# debugger.net
KiCad netlist of a schematic drawn in Altium Designer
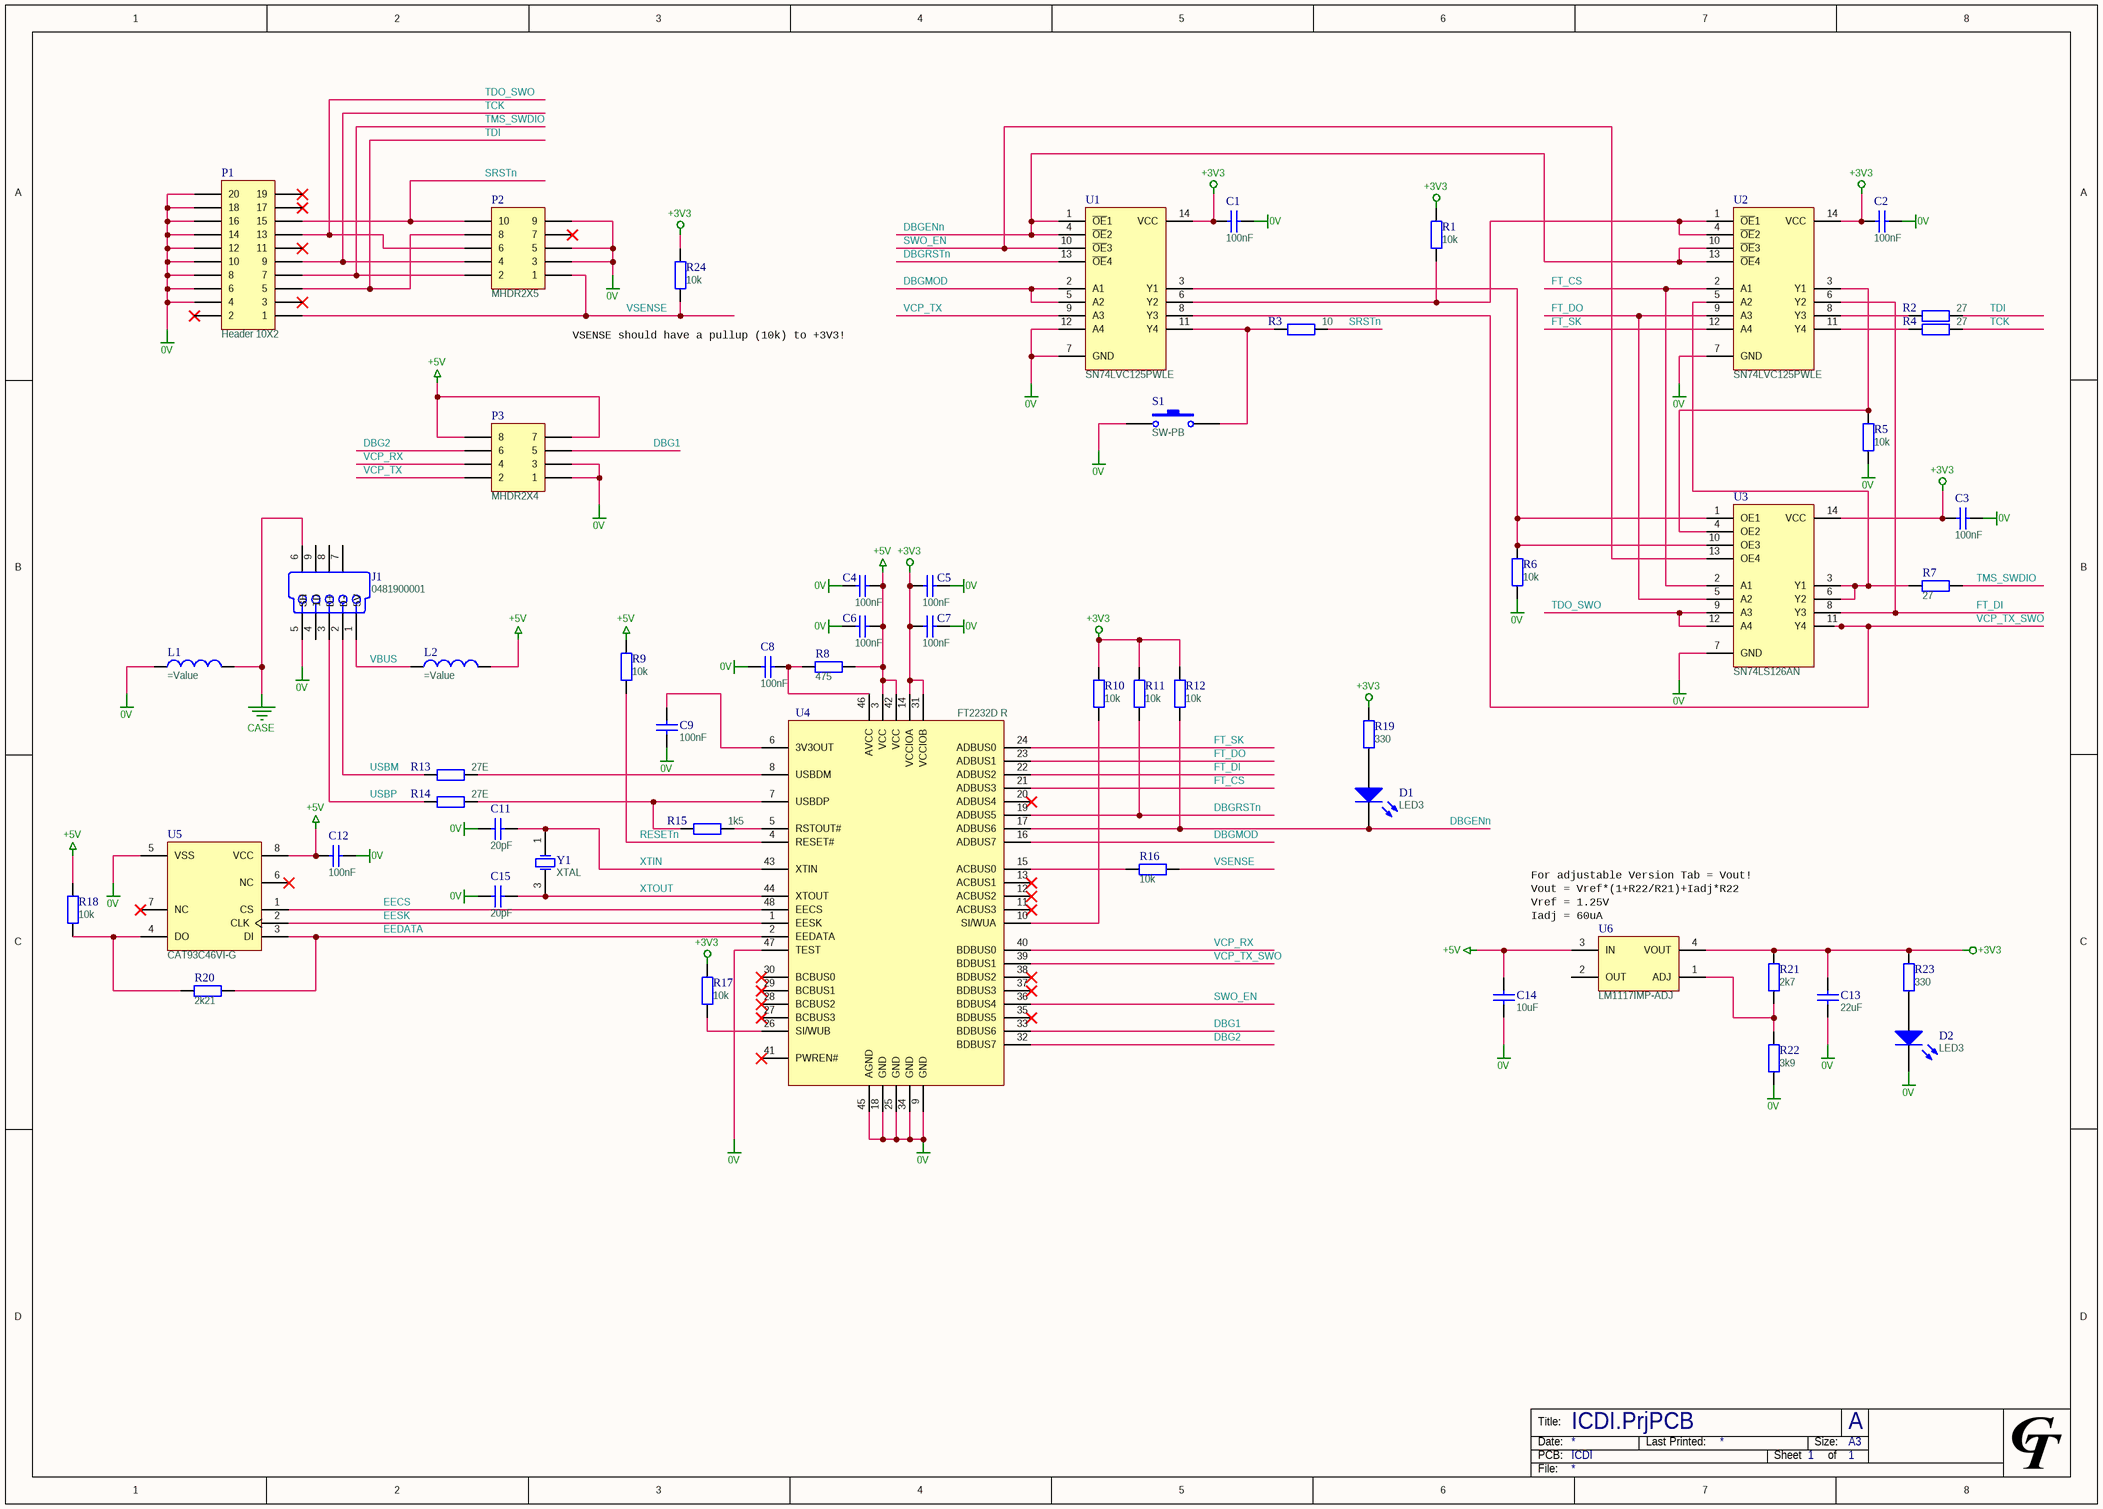
[diagram p0: debugger.SchDoc]

(export (version "E")
  (design (tool "Eeschema 10.0.6"))
  (components
    (comp (ref "C1")
      (value "100nF")
      (footprint "0603")
      (description "Capacitor")
      (libsource (lib "Miscellaneous Devices") (part "Cap"))
    )
    (comp (ref "C2")
      (value "100nF")
      (footprint "0603")
      (description "Capacitor")
      (libsource (lib "Miscellaneous Devices") (part "Cap"))
    )
    (comp (ref "C3")
      (value "100nF")
      (footprint "0603")
      (description "Capacitor")
      (libsource (lib "Miscellaneous Devices") (part "Cap"))
    )
    (comp (ref "C4")
      (value "100nF")
      (footprint "0603")
      (description "Capacitor")
      (libsource (lib "Miscellaneous Devices") (part "Cap"))
    )
    (comp (ref "C5")
      (value "100nF")
      (footprint "0603")
      (description "Capacitor")
      (libsource (lib "Miscellaneous Devices") (part "Cap"))
    )
    (comp (ref "C6")
      (value "100nF")
      (footprint "0603")
      (description "Capacitor")
      (libsource (lib "Miscellaneous Devices") (part "Cap"))
    )
    (comp (ref "C7")
      (value "100nF")
      (footprint "0603")
      (description "Capacitor")
      (libsource (lib "Miscellaneous Devices") (part "Cap"))
    )
    (comp (ref "C8")
      (value "100nF")
      (footprint "0603")
      (description "Capacitor")
      (libsource (lib "Miscellaneous Devices") (part "Cap"))
    )
    (comp (ref "C9")
      (value "100nF")
      (footprint "0603")
      (description "Capacitor")
      (libsource (lib "Miscellaneous Devices") (part "Cap"))
    )
    (comp (ref "C11")
      (value "20pF")
      (footprint "0603")
      (description "Capacitor")
      (libsource (lib "Miscellaneous Devices") (part "Cap"))
    )
    (comp (ref "C12")
      (value "100nF")
      (footprint "0603")
      (description "Capacitor")
      (libsource (lib "Miscellaneous Devices") (part "Cap"))
    )
    (comp (ref "C13")
      (value "22uF")
      (footprint "1210")
      (description "Capacitor")
      (libsource (lib "Miscellaneous Devices") (part "Cap"))
    )
    (comp (ref "C14")
      (value "10uF")
      (footprint "1210")
      (description "Capacitor")
      (libsource (lib "Miscellaneous Devices") (part "Cap"))
    )
    (comp (ref "C15")
      (value "20pF")
      (footprint "0603")
      (description "Capacitor")
      (libsource (lib "Miscellaneous Devices") (part "Cap"))
    )
    (comp (ref "D1")
      (value "LED3")
      (footprint "0805_L")
      (description "Typical BLUE SiC LED")
      (fields (field (name "MANUFACTURER") "ROHM"))
      (libsource (lib "Miscellaneous Devices") (part "LED3"))
    )
    (comp (ref "D2")
      (value "LED3")
      (footprint "0805_L")
      (description "Typical BLUE SiC LED")
      (fields (field (name "MANUFACTURER") "ROHM"))
      (libsource (lib "Miscellaneous Devices") (part "LED3"))
    )
    (comp (ref "J1")
      (value "0481900001")
      (footprint "481900001")
      (fields (field (name "MANUFACTURER") "Hirose"))
      (libsource (lib "ICDI") (part "0481900001"))
    )
    (comp (ref "L1")
      (value "~")
      (footprint "0603")
      (description "Inductor")
      (fields (field (name "MANUFACTURER") "PANASONIC"))
      (libsource (lib "Miscellaneous Devices") (part "Inductor"))
    )
    (comp (ref "L2")
      (value "~")
      (footprint "0603")
      (description "Inductor")
      (fields (field (name "MANUFACTURER") "PANASONIC"))
      (libsource (lib "Miscellaneous Devices") (part "Inductor"))
    )
    (comp (ref "P1")
      (value "Header 10X2")
      (footprint "HDR2X10")
      (description "Header, 10-Pin, Dual row")
      (fields (field (name "MANUFACTURER") "FCI"))
      (libsource (lib "Miscellaneous Connectors") (part "Header 10X2"))
    )
    (comp (ref "P2")
      (value "MHDR2X5")
      (footprint "MHDR2X5")
      (description "Header, 5-Pin, Dual row")
      (fields (field (name "MANUFACTURER") "MULTICOMP"))
      (libsource (lib "Miscellaneous Connectors") (part "MHDR2X5"))
    )
    (comp (ref "P3")
      (value "MHDR2X4")
      (footprint "MHDR2X4")
      (description "Header, 4-Pin, Dual row")
      (fields (field (name "MANUFACTURER") "MULTICOMP"))
      (libsource (lib "Miscellaneous Connectors") (part "MHDR2X4"))
    )
    (comp (ref "R1")
      (value "10k")
      (footprint "0603")
      (description "Resistor")
      (libsource (lib "Miscellaneous Devices") (part "Res2"))
    )
    (comp (ref "R2")
      (value "27")
      (footprint "0603")
      (description "Resistor")
      (libsource (lib "") (part "Res2_2"))
    )
    (comp (ref "R3")
      (value "10")
      (footprint "0603")
      (description "Resistor")
      (libsource (lib "") (part "Res2_2"))
    )
    (comp (ref "R4")
      (value "27")
      (footprint "0603")
      (description "Resistor")
      (libsource (lib "") (part "Res2_2"))
    )
    (comp (ref "R5")
      (value "10k")
      (footprint "0603")
      (description "Resistor")
      (libsource (lib "Miscellaneous Devices") (part "Res2"))
    )
    (comp (ref "R6")
      (value "10k")
      (footprint "0603")
      (description "Resistor")
      (libsource (lib "Miscellaneous Devices") (part "Res2"))
    )
    (comp (ref "R7")
      (value "27")
      (footprint "0603")
      (description "Resistor")
      (libsource (lib "") (part "Res2_2"))
    )
    (comp (ref "R8")
      (value "475")
      (footprint "0603")
      (description "Resistor")
      (libsource (lib "") (part "Res2_3"))
    )
    (comp (ref "R9")
      (value "10k")
      (footprint "0603")
      (description "Resistor")
      (libsource (lib "Miscellaneous Devices") (part "Res2"))
    )
    (comp (ref "R10")
      (value "10k")
      (footprint "0603")
      (description "Resistor")
      (libsource (lib "Miscellaneous Devices") (part "Res2"))
    )
    (comp (ref "R11")
      (value "10k")
      (footprint "0603")
      (description "Resistor")
      (libsource (lib "Miscellaneous Devices") (part "Res2"))
    )
    (comp (ref "R12")
      (value "10k")
      (footprint "0603")
      (description "Resistor")
      (libsource (lib "Miscellaneous Devices") (part "Res2"))
    )
    (comp (ref "R13")
      (value "27E")
      (footprint "0603")
      (description "Resistor")
      (libsource (lib "") (part "Res2_2"))
    )
    (comp (ref "R14")
      (value "27E")
      (footprint "0603")
      (description "Resistor")
      (libsource (lib "") (part "Res2_2"))
    )
    (comp (ref "R15")
      (value "1k5")
      (footprint "0603")
      (description "Resistor")
      (libsource (lib "") (part "Res2_2"))
    )
    (comp (ref "R16")
      (value "10k")
      (footprint "0603")
      (description "Resistor")
      (libsource (lib "") (part "Res2_2"))
    )
    (comp (ref "R17")
      (value "10k")
      (footprint "0603")
      (description "Resistor")
      (libsource (lib "Miscellaneous Devices") (part "Res2"))
    )
    (comp (ref "R18")
      (value "10k")
      (footprint "0603")
      (description "Resistor")
      (libsource (lib "Miscellaneous Devices") (part "Res2"))
    )
    (comp (ref "R19")
      (value "330")
      (footprint "0603")
      (description "Resistor")
      (libsource (lib "") (part "Res2_1"))
    )
    (comp (ref "R20")
      (value "2k21")
      (footprint "0603")
      (description "Resistor")
      (libsource (lib "") (part "Res2_2"))
    )
    (comp (ref "R21")
      (value "2k7")
      (footprint "0603")
      (description "Resistor")
      (libsource (lib "Miscellaneous Devices") (part "Res2"))
    )
    (comp (ref "R22")
      (value "3k9")
      (footprint "0603")
      (description "Resistor")
      (libsource (lib "Miscellaneous Devices") (part "Res2"))
    )
    (comp (ref "R23")
      (value "330")
      (footprint "0603")
      (description "Resistor")
      (libsource (lib "") (part "Res2_1"))
    )
    (comp (ref "R24")
      (value "10k")
      (footprint "0603")
      (description "Resistor")
      (libsource (lib "Miscellaneous Devices") (part "Res2"))
    )
    (comp (ref "S1")
      (value "SW-PB")
      (footprint "PUSHBTN")
      (description "Switch")
      (libsource (lib "Miscellaneous Devices") (part "SW-PB"))
    )
    (comp (ref "U1")
      (value "SN74LVC125PWLE")
      (footprint "PW014_N")
      (description "Quadruple Bus Buffer Gate with 3-State Outputs")
      (fields (field (name "MANUFACTURER") "TEXAS INSTRUMENTS"))
      (libsource (lib "TI Logic Buffer Line Driver") (part "SN74LVC125PWLE"))
    )
    (comp (ref "U2")
      (value "SN74LVC125PWLE")
      (footprint "PW014_N")
      (description "Quadruple Bus Buffer Gate with 3-State Outputs")
      (fields (field (name "MANUFACTURER") "TEXAS INSTRUMENTS"))
      (libsource (lib "TI Logic Buffer Line Driver") (part "SN74LVC125PWLE"))
    )
    (comp (ref "U3")
      (value "SN74LS126AN")
      (footprint "PW014_N")
      (description "Quadruple Bus Buffer with 3-State Outputs")
      (fields (field (name "MANUFACTURER") "TEXAS INSTRUMENTS"))
      (libsource (lib "TI Logic Buffer Line Driver") (part "SN74LS126AN"))
    )
    (comp (ref "U4")
      (value "FT2232D R")
      (footprint "LQFP-48_N")
      (description "Dual USB UART/FIFO Chip, LQFP-48")
      (fields (field (name "MANUFACTURER") "FTDI"))
      (libsource (lib "FTDI Communication UART") (part "FT2232C"))
    )
    (comp (ref "U5")
      (value "CAT93C46VI-G")
      (footprint "SOIC-SN8_N")
      (description "1K, 64xEEPROM, 1K, 64X16, MICROWIRE, SOIC8")
      (fields (field (name "MANUFACTURER") "CATALYST SEMICONDUCTOR"))
      (libsource (lib "Microchip Memory Microwire Serial EEPROM") (part "93C46B-I/SN"))
    )
    (comp (ref "U6")
      (value "LM1117IMP-ADJ")
      (footprint "MP04A_N")
      (description "800mA Low-Dropout Linear Regulator")
      (fields (field (name "MANUFACTURER") "NATIONAL SEMICONDUCTOR"))
      (libsource (lib "ICDI_1") (part "LM1117IMP-ADJ"))
    )
    (comp (ref "Y1")
      (value "XTAL")
      (footprint "xtal")
      (description "Crystal Oscillator")
      (fields (field (name "MANUFACTURER") "SIWARD"))
      (libsource (lib "ICDI") (part "XTAL"))
    )
  )
  (nets
    (net (code "1") (name "+3V3") (class "Default")
      (node (ref "C1") (pin "1") (pinfunction "1_1") (pintype "passive"))
      (node (ref "C13") (pin "2") (pinfunction "2_2") (pintype "passive"))
      (node (ref "C2") (pin "1") (pinfunction "1_1") (pintype "passive"))
      (node (ref "C3") (pin "1") (pinfunction "1_1") (pintype "passive"))
      (node (ref "C5") (pin "1") (pinfunction "1_1") (pintype "passive"))
      (node (ref "C7") (pin "1") (pinfunction "1_1") (pintype "passive"))
      (node (ref "R1") (pin "2") (pinfunction "2_2") (pintype "passive"))
      (node (ref "R10") (pin "2") (pinfunction "2_2") (pintype "passive"))
      (node (ref "R11") (pin "2") (pinfunction "2_2") (pintype "passive"))
      (node (ref "R12") (pin "2") (pinfunction "2_2") (pintype "passive"))
      (node (ref "R17") (pin "2") (pinfunction "2_2") (pintype "passive"))
      (node (ref "R19") (pin "1") (pinfunction "1_1") (pintype "passive"))
      (node (ref "R21") (pin "2") (pinfunction "2_2") (pintype "passive"))
      (node (ref "R23") (pin "1") (pinfunction "1_1") (pintype "passive"))
      (node (ref "R24") (pin "2") (pinfunction "2_2") (pintype "passive"))
      (node (ref "U1") (pin "14") (pinfunction "VCC_14") (pintype "passive"))
      (node (ref "U2") (pin "14") (pinfunction "VCC_14") (pintype "passive"))
      (node (ref "U3") (pin "14") (pinfunction "VCC_14") (pintype "passive"))
      (node (ref "U4") (pin "14") (pinfunction "VCCIOA_14") (pintype "passive"))
      (node (ref "U4") (pin "31") (pinfunction "VCCIOB_31") (pintype "passive"))
      (node (ref "U6") (pin "4") (pinfunction "VOUT_4") (pintype "power_in"))
    )
    (net (code "2") (name "+5V") (class "Default")
      (node (ref "C12") (pin "1") (pinfunction "1_1") (pintype "passive"))
      (node (ref "C14") (pin "2") (pinfunction "2_2") (pintype "passive"))
      (node (ref "C4") (pin "1") (pinfunction "1_1") (pintype "passive"))
      (node (ref "C6") (pin "2") (pinfunction "2_2") (pintype "passive"))
      (node (ref "L2") (pin "2") (pinfunction "2_2") (pintype "passive"))
      (node (ref "P3") (pin "7") (pinfunction "7_7") (pintype "passive"))
      (node (ref "P3") (pin "8") (pinfunction "8_8") (pintype "passive"))
      (node (ref "R18") (pin "2") (pinfunction "2_2") (pintype "passive"))
      (node (ref "R8") (pin "1") (pinfunction "1_1") (pintype "passive"))
      (node (ref "R9") (pin "2") (pinfunction "2_2") (pintype "passive"))
      (node (ref "U4") (pin "3") (pinfunction "VCC_3") (pintype "passive"))
      (node (ref "U4") (pin "42") (pinfunction "VCC_42") (pintype "passive"))
      (node (ref "U5") (pin "8") (pinfunction "VCC_8") (pintype "passive"))
      (node (ref "U6") (pin "3") (pinfunction "IN_3") (pintype "power_in"))
    )
    (net (code "3") (name "/DBG1") (class "Default")
      (node (ref "P3") (pin "5") (pinfunction "5_5") (pintype "passive"))
      (node (ref "U4") (pin "33") (pinfunction "BDBUS6_33") (pintype "passive"))
    )
    (net (code "4") (name "/DBG2") (class "Default")
      (node (ref "P3") (pin "6") (pinfunction "6_6") (pintype "passive"))
      (node (ref "U4") (pin "32") (pinfunction "BDBUS7_32") (pintype "passive"))
    )
    (net (code "5") (name "/DBGENn") (class "Default")
      (node (ref "D1") (pin "2") (pinfunction "K_2") (pintype "passive"))
      (node (ref "R12") (pin "1") (pinfunction "1_1") (pintype "passive"))
      (node (ref "U1") (pin "1") (pinfunction "~{OE}1_1") (pintype "passive"))
      (node (ref "U1") (pin "4") (pinfunction "~{OE}2_4") (pintype "passive"))
      (node (ref "U2") (pin "10") (pinfunction "~{OE}3_10") (pintype "passive"))
      (node (ref "U2") (pin "13") (pinfunction "~{OE}4_13") (pintype "passive"))
      (node (ref "U4") (pin "17") (pinfunction "ADBUS6_17") (pintype "passive"))
    )
    (net (code "6") (name "/DBGMOD") (class "Default")
      (node (ref "U1") (pin "2") (pinfunction "A1_2") (pintype "passive"))
      (node (ref "U1") (pin "5") (pinfunction "A2_5") (pintype "passive"))
      (node (ref "U4") (pin "16") (pinfunction "ADBUS7_16") (pintype "passive"))
    )
    (net (code "7") (name "/DBGRSTn") (class "Default")
      (node (ref "R11") (pin "1") (pinfunction "1_1") (pintype "passive"))
      (node (ref "U1") (pin "13") (pinfunction "~{OE}4_13") (pintype "passive"))
      (node (ref "U4") (pin "19") (pinfunction "ADBUS5_19") (pintype "passive"))
    )
    (net (code "8") (name "/EECS") (class "Default")
      (node (ref "U4") (pin "48") (pinfunction "EECS_48") (pintype "passive"))
      (node (ref "U5") (pin "1") (pinfunction "CS_1") (pintype "passive"))
    )
    (net (code "9") (name "/EEDATA") (class "Default")
      (node (ref "R20") (pin "2") (pinfunction "2_2") (pintype "passive"))
      (node (ref "U4") (pin "2") (pinfunction "EEDATA_2") (pintype "passive"))
      (node (ref "U5") (pin "3") (pinfunction "DI_3") (pintype "passive"))
    )
    (net (code "10") (name "/EESK") (class "Default")
      (node (ref "U4") (pin "1") (pinfunction "EESK_1") (pintype "passive"))
      (node (ref "U5") (pin "2") (pinfunction "CLK_2") (pintype "passive"))
    )
    (net (code "11") (name "/FT_CS") (class "Default")
      (node (ref "U2") (pin "2") (pinfunction "A1_2") (pintype "passive"))
      (node (ref "U3") (pin "2") (pinfunction "A1_2") (pintype "passive"))
      (node (ref "U4") (pin "21") (pinfunction "ADBUS3_21") (pintype "passive"))
    )
    (net (code "12") (name "/FT_DI") (class "Default")
      (node (ref "U2") (pin "6") (pinfunction "Y2_6") (pintype "passive"))
      (node (ref "U3") (pin "8") (pinfunction "Y3_8") (pintype "passive"))
      (node (ref "U4") (pin "22") (pinfunction "ADBUS2_22") (pintype "passive"))
    )
    (net (code "13") (name "/FT_DO") (class "Default")
      (node (ref "U2") (pin "9") (pinfunction "A3_9") (pintype "passive"))
      (node (ref "U3") (pin "5") (pinfunction "A2_5") (pintype "passive"))
      (node (ref "U4") (pin "23") (pinfunction "ADBUS1_23") (pintype "passive"))
    )
    (net (code "14") (name "/FT_SK") (class "Default")
      (node (ref "U2") (pin "12") (pinfunction "A4_12") (pintype "passive"))
      (node (ref "U4") (pin "24") (pinfunction "ADBUS0_24") (pintype "passive"))
    )
    (net (code "15") (name "/RESETn") (class "Default")
      (node (ref "R9") (pin "1") (pinfunction "1_1") (pintype "passive"))
      (node (ref "U4") (pin "4") (pinfunction "RESET#_4") (pintype "passive"))
    )
    (net (code "16") (name "/SRSTn") (class "Default")
      (node (ref "P1") (pin "15") (pinfunction "15_15") (pintype "passive"))
      (node (ref "P2") (pin "10") (pinfunction "10_10") (pintype "passive"))
      (node (ref "R3") (pin "2") (pinfunction "2_2") (pintype "passive"))
    )
    (net (code "17") (name "/SWO_EN") (class "Default")
      (node (ref "U1") (pin "10") (pinfunction "~{OE}3_10") (pintype "passive"))
      (node (ref "U3") (pin "13") (pinfunction "OE4_13") (pintype "passive"))
      (node (ref "U4") (pin "36") (pinfunction "BDBUS4_36") (pintype "passive"))
    )
    (net (code "18") (name "/TCK") (class "Default")
      (node (ref "P1") (pin "9") (pinfunction "9_9") (pintype "passive"))
      (node (ref "P2") (pin "4") (pinfunction "4_4") (pintype "passive"))
      (node (ref "R4") (pin "2") (pinfunction "2_2") (pintype "passive"))
    )
    (net (code "19") (name "/TDI") (class "Default")
      (node (ref "P1") (pin "5") (pinfunction "5_5") (pintype "passive"))
      (node (ref "P2") (pin "8") (pinfunction "8_8") (pintype "passive"))
      (node (ref "R2") (pin "2") (pinfunction "2_2") (pintype "passive"))
    )
    (net (code "20") (name "/TDO_SWO") (class "Default")
      (node (ref "P1") (pin "13") (pinfunction "13_13") (pintype "passive"))
      (node (ref "P2") (pin "6") (pinfunction "6_6") (pintype "passive"))
      (node (ref "U3") (pin "12") (pinfunction "A4_12") (pintype "passive"))
      (node (ref "U3") (pin "9") (pinfunction "A3_9") (pintype "passive"))
    )
    (net (code "21") (name "/TMS_SWDIO") (class "Default")
      (node (ref "P1") (pin "7") (pinfunction "7_7") (pintype "passive"))
      (node (ref "P2") (pin "2") (pinfunction "2_2") (pintype "passive"))
      (node (ref "R7") (pin "2") (pinfunction "2_2") (pintype "passive"))
    )
    (net (code "22") (name "/USBM") (class "Default")
      (node (ref "J1") (pin "2") (pinfunction "D-_2") (pintype "passive"))
      (node (ref "R13") (pin "1") (pinfunction "1_1") (pintype "passive"))
    )
    (net (code "23") (name "/USBP") (class "Default")
      (node (ref "J1") (pin "3") (pinfunction "D+_3") (pintype "passive"))
      (node (ref "R14") (pin "1") (pinfunction "1_1") (pintype "passive"))
    )
    (net (code "24") (name "/VBUS") (class "Default")
      (node (ref "J1") (pin "1") (pinfunction "V_BUS_(5V)_1") (pintype "passive"))
      (node (ref "L2") (pin "1") (pinfunction "1_1") (pintype "passive"))
    )
    (net (code "25") (name "/VCP_RX") (class "Default")
      (node (ref "P3") (pin "4") (pinfunction "4_4") (pintype "passive"))
      (node (ref "U4") (pin "40") (pinfunction "BDBUS0_40") (pintype "passive"))
    )
    (net (code "26") (name "/VCP_TX") (class "Default")
      (node (ref "P3") (pin "2") (pinfunction "2_2") (pintype "passive"))
      (node (ref "U1") (pin "9") (pinfunction "A3_9") (pintype "passive"))
    )
    (net (code "27") (name "/VCP_TX_SWO") (class "Default")
      (node (ref "U1") (pin "8") (pinfunction "Y3_8") (pintype "passive"))
      (node (ref "U3") (pin "11") (pinfunction "Y4_11") (pintype "passive"))
      (node (ref "U4") (pin "39") (pinfunction "BDBUS1_39") (pintype "passive"))
    )
    (net (code "28") (name "/VSENSE") (class "Default")
      (node (ref "P1") (pin "1") (pinfunction "1_1") (pintype "passive"))
      (node (ref "P2") (pin "1") (pinfunction "1_1") (pintype "passive"))
      (node (ref "R16") (pin "2") (pinfunction "2_2") (pintype "passive"))
      (node (ref "R24") (pin "1") (pinfunction "1_1") (pintype "passive"))
    )
    (net (code "29") (name "/XTIN") (class "Default")
      (node (ref "C11") (pin "1") (pinfunction "1_1") (pintype "passive"))
      (node (ref "U4") (pin "43") (pinfunction "XTIN_43") (pintype "passive"))
      (node (ref "Y1") (pin "1") (pinfunction "OSC1_1") (pintype "passive"))
    )
    (net (code "30") (name "/XTOUT") (class "Default")
      (node (ref "C15") (pin "1") (pinfunction "1_1") (pintype "passive"))
      (node (ref "U4") (pin "44") (pinfunction "XTOUT_44") (pintype "passive"))
      (node (ref "Y1") (pin "3") (pinfunction "OSC2_3") (pintype "passive"))
    )
    (net (code "31") (name "0V") (class "Default")
      (node (ref "C1") (pin "2") (pinfunction "2_2") (pintype "passive"))
      (node (ref "C11") (pin "2") (pinfunction "2_2") (pintype "passive"))
      (node (ref "C12") (pin "2") (pinfunction "2_2") (pintype "passive"))
      (node (ref "C13") (pin "1") (pinfunction "1_1") (pintype "passive"))
      (node (ref "C14") (pin "1") (pinfunction "1_1") (pintype "passive"))
      (node (ref "C15") (pin "2") (pinfunction "2_2") (pintype "passive"))
      (node (ref "C2") (pin "2") (pinfunction "2_2") (pintype "passive"))
      (node (ref "C3") (pin "2") (pinfunction "2_2") (pintype "passive"))
      (node (ref "C4") (pin "2") (pinfunction "2_2") (pintype "passive"))
      (node (ref "C5") (pin "2") (pinfunction "2_2") (pintype "passive"))
      (node (ref "C6") (pin "1") (pinfunction "1_1") (pintype "passive"))
      (node (ref "C7") (pin "2") (pinfunction "2_2") (pintype "passive"))
      (node (ref "C8") (pin "1") (pinfunction "1_1") (pintype "passive"))
      (node (ref "C9") (pin "1") (pinfunction "1_1") (pintype "passive"))
      (node (ref "D2") (pin "2") (pinfunction "K_2") (pintype "passive"))
      (node (ref "J1") (pin "5") (pinfunction "GND_5") (pintype "passive"))
      (node (ref "L1") (pin "1") (pinfunction "1_1") (pintype "passive"))
      (node (ref "P1") (pin "10") (pinfunction "10_10") (pintype "passive"))
      (node (ref "P1") (pin "12") (pinfunction "12_12") (pintype "passive"))
      (node (ref "P1") (pin "14") (pinfunction "14_14") (pintype "passive"))
      (node (ref "P1") (pin "16") (pinfunction "16_16") (pintype "passive"))
      (node (ref "P1") (pin "18") (pinfunction "18_18") (pintype "passive"))
      (node (ref "P1") (pin "20") (pinfunction "20_20") (pintype "passive"))
      (node (ref "P1") (pin "4") (pinfunction "4_4") (pintype "passive"))
      (node (ref "P1") (pin "6") (pinfunction "6_6") (pintype "passive"))
      (node (ref "P1") (pin "8") (pinfunction "8_8") (pintype "passive"))
      (node (ref "P2") (pin "3") (pinfunction "3_3") (pintype "passive"))
      (node (ref "P2") (pin "5") (pinfunction "5_5") (pintype "passive"))
      (node (ref "P2") (pin "9") (pinfunction "9_9") (pintype "passive"))
      (node (ref "P3") (pin "1") (pinfunction "1_1") (pintype "passive"))
      (node (ref "P3") (pin "3") (pinfunction "3_3") (pintype "passive"))
      (node (ref "R22") (pin "1") (pinfunction "1_1") (pintype "passive"))
      (node (ref "R5") (pin "1") (pinfunction "1_1") (pintype "passive"))
      (node (ref "R6") (pin "1") (pinfunction "1_1") (pintype "passive"))
      (node (ref "S1") (pin "1") (pinfunction "1_1") (pintype "passive"))
      (node (ref "U1") (pin "12") (pinfunction "A4_12") (pintype "passive"))
      (node (ref "U1") (pin "7") (pinfunction "GND_7") (pintype "passive"))
      (node (ref "U2") (pin "7") (pinfunction "GND_7") (pintype "passive"))
      (node (ref "U3") (pin "7") (pinfunction "GND_7") (pintype "passive"))
      (node (ref "U4") (pin "18") (pinfunction "GND_18") (pintype "passive"))
      (node (ref "U4") (pin "25") (pinfunction "GND_25") (pintype "passive"))
      (node (ref "U4") (pin "34") (pinfunction "GND_34") (pintype "passive"))
      (node (ref "U4") (pin "45") (pinfunction "AGND_45") (pintype "passive"))
      (node (ref "U4") (pin "47") (pinfunction "TEST_47") (pintype "passive"))
      (node (ref "U4") (pin "9") (pinfunction "GND_9") (pintype "passive"))
      (node (ref "U5") (pin "5") (pinfunction "VSS_5") (pintype "passive"))
    )
    (net (code "32") (name "CASE") (class "Default")
      (node (ref "J1") (pin "6") (pinfunction "Tab_6") (pintype "passive"))
      (node (ref "L1") (pin "2") (pinfunction "2_2") (pintype "passive"))
    )
    (net (code "33") (name "Net-(D1-A)") (class "Default")
      (node (ref "D1") (pin "1") (pinfunction "A_1") (pintype "passive"))
      (node (ref "R19") (pin "2") (pinfunction "2_2") (pintype "passive"))
    )
    (net (code "34") (name "Net-(D2-A)") (class "Default")
      (node (ref "D2") (pin "1") (pinfunction "A_1") (pintype "passive"))
      (node (ref "R23") (pin "2") (pinfunction "2_2") (pintype "passive"))
    )
    (net (code "35") (name "Net-(U1-Y1)") (class "Default")
      (node (ref "R6") (pin "2") (pinfunction "2_2") (pintype "passive"))
      (node (ref "U1") (pin "3") (pinfunction "Y1_3") (pintype "passive"))
      (node (ref "U3") (pin "1") (pinfunction "OE1_1") (pintype "passive"))
      (node (ref "U3") (pin "10") (pinfunction "OE3_10") (pintype "passive"))
    )
    (net (code "36") (name "Net-(U1-Y2)") (class "Default")
      (node (ref "R1") (pin "1") (pinfunction "1_1") (pintype "passive"))
      (node (ref "U1") (pin "6") (pinfunction "Y2_6") (pintype "passive"))
      (node (ref "U2") (pin "1") (pinfunction "~{OE}1_1") (pintype "passive"))
      (node (ref "U2") (pin "4") (pinfunction "~{OE}2_4") (pintype "passive"))
    )
    (net (code "37") (name "Net-(U1-Y4)") (class "Default")
      (node (ref "R3") (pin "1") (pinfunction "1_1") (pintype "passive"))
      (node (ref "S1") (pin "2") (pinfunction "2_2") (pintype "passive"))
      (node (ref "U1") (pin "11") (pinfunction "Y4_11") (pintype "passive"))
    )
    (net (code "38") (name "Net-(U2-A2)") (class "Default")
      (node (ref "R7") (pin "1") (pinfunction "1_1") (pintype "passive"))
      (node (ref "U2") (pin "5") (pinfunction "A2_5") (pintype "passive"))
      (node (ref "U3") (pin "3") (pinfunction "Y1_3") (pintype "passive"))
      (node (ref "U3") (pin "6") (pinfunction "Y2_6") (pintype "passive"))
    )
    (net (code "39") (name "Net-(U2-Y1)") (class "Default")
      (node (ref "R5") (pin "2") (pinfunction "2_2") (pintype "passive"))
      (node (ref "U2") (pin "3") (pinfunction "Y1_3") (pintype "passive"))
      (node (ref "U3") (pin "4") (pinfunction "OE2_4") (pintype "passive"))
    )
    (net (code "40") (name "Net-(U2-Y3)") (class "Default")
      (node (ref "R2") (pin "1") (pinfunction "1_1") (pintype "passive"))
      (node (ref "U2") (pin "8") (pinfunction "Y3_8") (pintype "passive"))
    )
    (net (code "41") (name "Net-(U2-Y4)") (class "Default")
      (node (ref "R4") (pin "1") (pinfunction "1_1") (pintype "passive"))
      (node (ref "U2") (pin "11") (pinfunction "Y4_11") (pintype "passive"))
    )
    (net (code "42") (name "Net-(U4-3V3OUT)") (class "Default")
      (node (ref "C9") (pin "2") (pinfunction "2_2") (pintype "passive"))
      (node (ref "U4") (pin "6") (pinfunction "3V3OUT_6") (pintype "passive"))
    )
    (net (code "43") (name "Net-(U4-ACBUS0)") (class "Default")
      (node (ref "R16") (pin "1") (pinfunction "1_1") (pintype "passive"))
      (node (ref "U4") (pin "15") (pinfunction "ACBUS0_15") (pintype "passive"))
    )
    (net (code "44") (name "Net-(U4-AVCC)") (class "Default")
      (node (ref "C8") (pin "2") (pinfunction "2_2") (pintype "passive"))
      (node (ref "R8") (pin "2") (pinfunction "2_2") (pintype "passive"))
      (node (ref "U4") (pin "46") (pinfunction "AVCC_46") (pintype "passive"))
    )
    (net (code "45") (name "Net-(U4-RSTOUT#)") (class "Default")
      (node (ref "R15") (pin "2") (pinfunction "2_2") (pintype "passive"))
      (node (ref "U4") (pin "5") (pinfunction "RSTOUT#_5") (pintype "passive"))
    )
    (net (code "46") (name "Net-(U4-SI{slash}WUA)") (class "Default")
      (node (ref "R10") (pin "1") (pinfunction "1_1") (pintype "passive"))
      (node (ref "U4") (pin "10") (pinfunction "SI/WUA_10") (pintype "passive"))
    )
    (net (code "47") (name "Net-(U4-SI{slash}WUB)") (class "Default")
      (node (ref "R17") (pin "1") (pinfunction "1_1") (pintype "passive"))
      (node (ref "U4") (pin "26") (pinfunction "SI/WUB_26") (pintype "passive"))
    )
    (net (code "48") (name "Net-(U4-USBDM)") (class "Default")
      (node (ref "R13") (pin "2") (pinfunction "2_2") (pintype "passive"))
      (node (ref "U4") (pin "8") (pinfunction "USBDM_8") (pintype "passive"))
    )
    (net (code "49") (name "Net-(U4-USBDP)") (class "Default")
      (node (ref "R14") (pin "2") (pinfunction "2_2") (pintype "passive"))
      (node (ref "R15") (pin "1") (pinfunction "1_1") (pintype "passive"))
      (node (ref "U4") (pin "7") (pinfunction "USBDP_7") (pintype "passive"))
    )
    (net (code "50") (name "Net-(U5-DO)") (class "Default")
      (node (ref "R18") (pin "1") (pinfunction "1_1") (pintype "passive"))
      (node (ref "R20") (pin "1") (pinfunction "1_1") (pintype "passive"))
      (node (ref "U5") (pin "4") (pinfunction "DO_4") (pintype "passive"))
    )
    (net (code "51") (name "Net-(U6-ADJ)") (class "Default")
      (node (ref "R21") (pin "1") (pinfunction "1_1") (pintype "passive"))
      (node (ref "R22") (pin "2") (pinfunction "2_2") (pintype "passive"))
      (node (ref "U6") (pin "1") (pinfunction "ADJ_1") (pintype "passive"))
    )
    (net (code "52") (name "unconnected-(J1-NC-Pad4)") (class "Default")
      (node (ref "J1") (pin "4") (pinfunction "NC_4") (pintype "passive"))
    )
    (net (code "53") (name "unconnected-(J1-Tab-Pad7)") (class "Default")
      (node (ref "J1") (pin "7") (pinfunction "Tab_7") (pintype "passive"))
    )
    (net (code "54") (name "unconnected-(J1-Tab-Pad8)") (class "Default")
      (node (ref "J1") (pin "8") (pinfunction "Tab_8") (pintype "passive"))
    )
    (net (code "55") (name "unconnected-(J1-Tab-Pad9)") (class "Default")
      (node (ref "J1") (pin "9") (pinfunction "Tab_9") (pintype "passive"))
    )
    (net (code "56") (name "unconnected-(P1-Pad2)") (class "Default")
      (node (ref "P1") (pin "2") (pinfunction "2_2") (pintype "passive+no_connect"))
    )
    (net (code "57") (name "unconnected-(P1-Pad3)") (class "Default")
      (node (ref "P1") (pin "3") (pinfunction "3_3") (pintype "passive+no_connect"))
    )
    (net (code "58") (name "unconnected-(P1-Pad11)") (class "Default")
      (node (ref "P1") (pin "11") (pinfunction "11_11") (pintype "passive+no_connect"))
    )
    (net (code "59") (name "unconnected-(P1-Pad17)") (class "Default")
      (node (ref "P1") (pin "17") (pinfunction "17_17") (pintype "passive+no_connect"))
    )
    (net (code "60") (name "unconnected-(P1-Pad19)") (class "Default")
      (node (ref "P1") (pin "19") (pinfunction "19_19") (pintype "passive+no_connect"))
    )
    (net (code "61") (name "unconnected-(P2-Pad7)") (class "Default")
      (node (ref "P2") (pin "7") (pinfunction "7_7") (pintype "passive+no_connect"))
    )
    (net (code "62") (name "unconnected-(U4-ACBUS1-Pad13)") (class "Default")
      (node (ref "U4") (pin "13") (pinfunction "ACBUS1_13") (pintype "passive+no_connect"))
    )
    (net (code "63") (name "unconnected-(U4-ACBUS2-Pad12)") (class "Default")
      (node (ref "U4") (pin "12") (pinfunction "ACBUS2_12") (pintype "passive+no_connect"))
    )
    (net (code "64") (name "unconnected-(U4-ACBUS3-Pad11)") (class "Default")
      (node (ref "U4") (pin "11") (pinfunction "ACBUS3_11") (pintype "passive+no_connect"))
    )
    (net (code "65") (name "unconnected-(U4-ADBUS4-Pad20)") (class "Default")
      (node (ref "U4") (pin "20") (pinfunction "ADBUS4_20") (pintype "passive+no_connect"))
    )
    (net (code "66") (name "unconnected-(U4-BCBUS0-Pad30)") (class "Default")
      (node (ref "U4") (pin "30") (pinfunction "BCBUS0_30") (pintype "passive+no_connect"))
    )
    (net (code "67") (name "unconnected-(U4-BCBUS1-Pad29)") (class "Default")
      (node (ref "U4") (pin "29") (pinfunction "BCBUS1_29") (pintype "passive+no_connect"))
    )
    (net (code "68") (name "unconnected-(U4-BCBUS2-Pad28)") (class "Default")
      (node (ref "U4") (pin "28") (pinfunction "BCBUS2_28") (pintype "passive+no_connect"))
    )
    (net (code "69") (name "unconnected-(U4-BCBUS3-Pad27)") (class "Default")
      (node (ref "U4") (pin "27") (pinfunction "BCBUS3_27") (pintype "passive+no_connect"))
    )
    (net (code "70") (name "unconnected-(U4-BDBUS2-Pad38)") (class "Default")
      (node (ref "U4") (pin "38") (pinfunction "BDBUS2_38") (pintype "passive+no_connect"))
    )
    (net (code "71") (name "unconnected-(U4-BDBUS3-Pad37)") (class "Default")
      (node (ref "U4") (pin "37") (pinfunction "BDBUS3_37") (pintype "passive+no_connect"))
    )
    (net (code "72") (name "unconnected-(U4-BDBUS5-Pad35)") (class "Default")
      (node (ref "U4") (pin "35") (pinfunction "BDBUS5_35") (pintype "passive+no_connect"))
    )
    (net (code "73") (name "unconnected-(U4-PWREN#-Pad41)") (class "Default")
      (node (ref "U4") (pin "41") (pinfunction "PWREN#_41") (pintype "passive+no_connect"))
    )
    (net (code "74") (name "unconnected-(U5-NC-Pad6)") (class "Default")
      (node (ref "U5") (pin "6") (pinfunction "NC_6") (pintype "passive+no_connect"))
    )
    (net (code "75") (name "unconnected-(U5-NC-Pad7)") (class "Default")
      (node (ref "U5") (pin "7") (pinfunction "NC_7") (pintype "passive+no_connect"))
    )
    (net (code "76") (name "unconnected-(U6-OUT-Pad2)") (class "Default")
      (node (ref "U6") (pin "2") (pinfunction "OUT_2") (pintype "power_in"))
    )
  )
)
